# SparkFun_Servo_Trigger.net
KiCad netlist of a schematic drawn in EAGLE
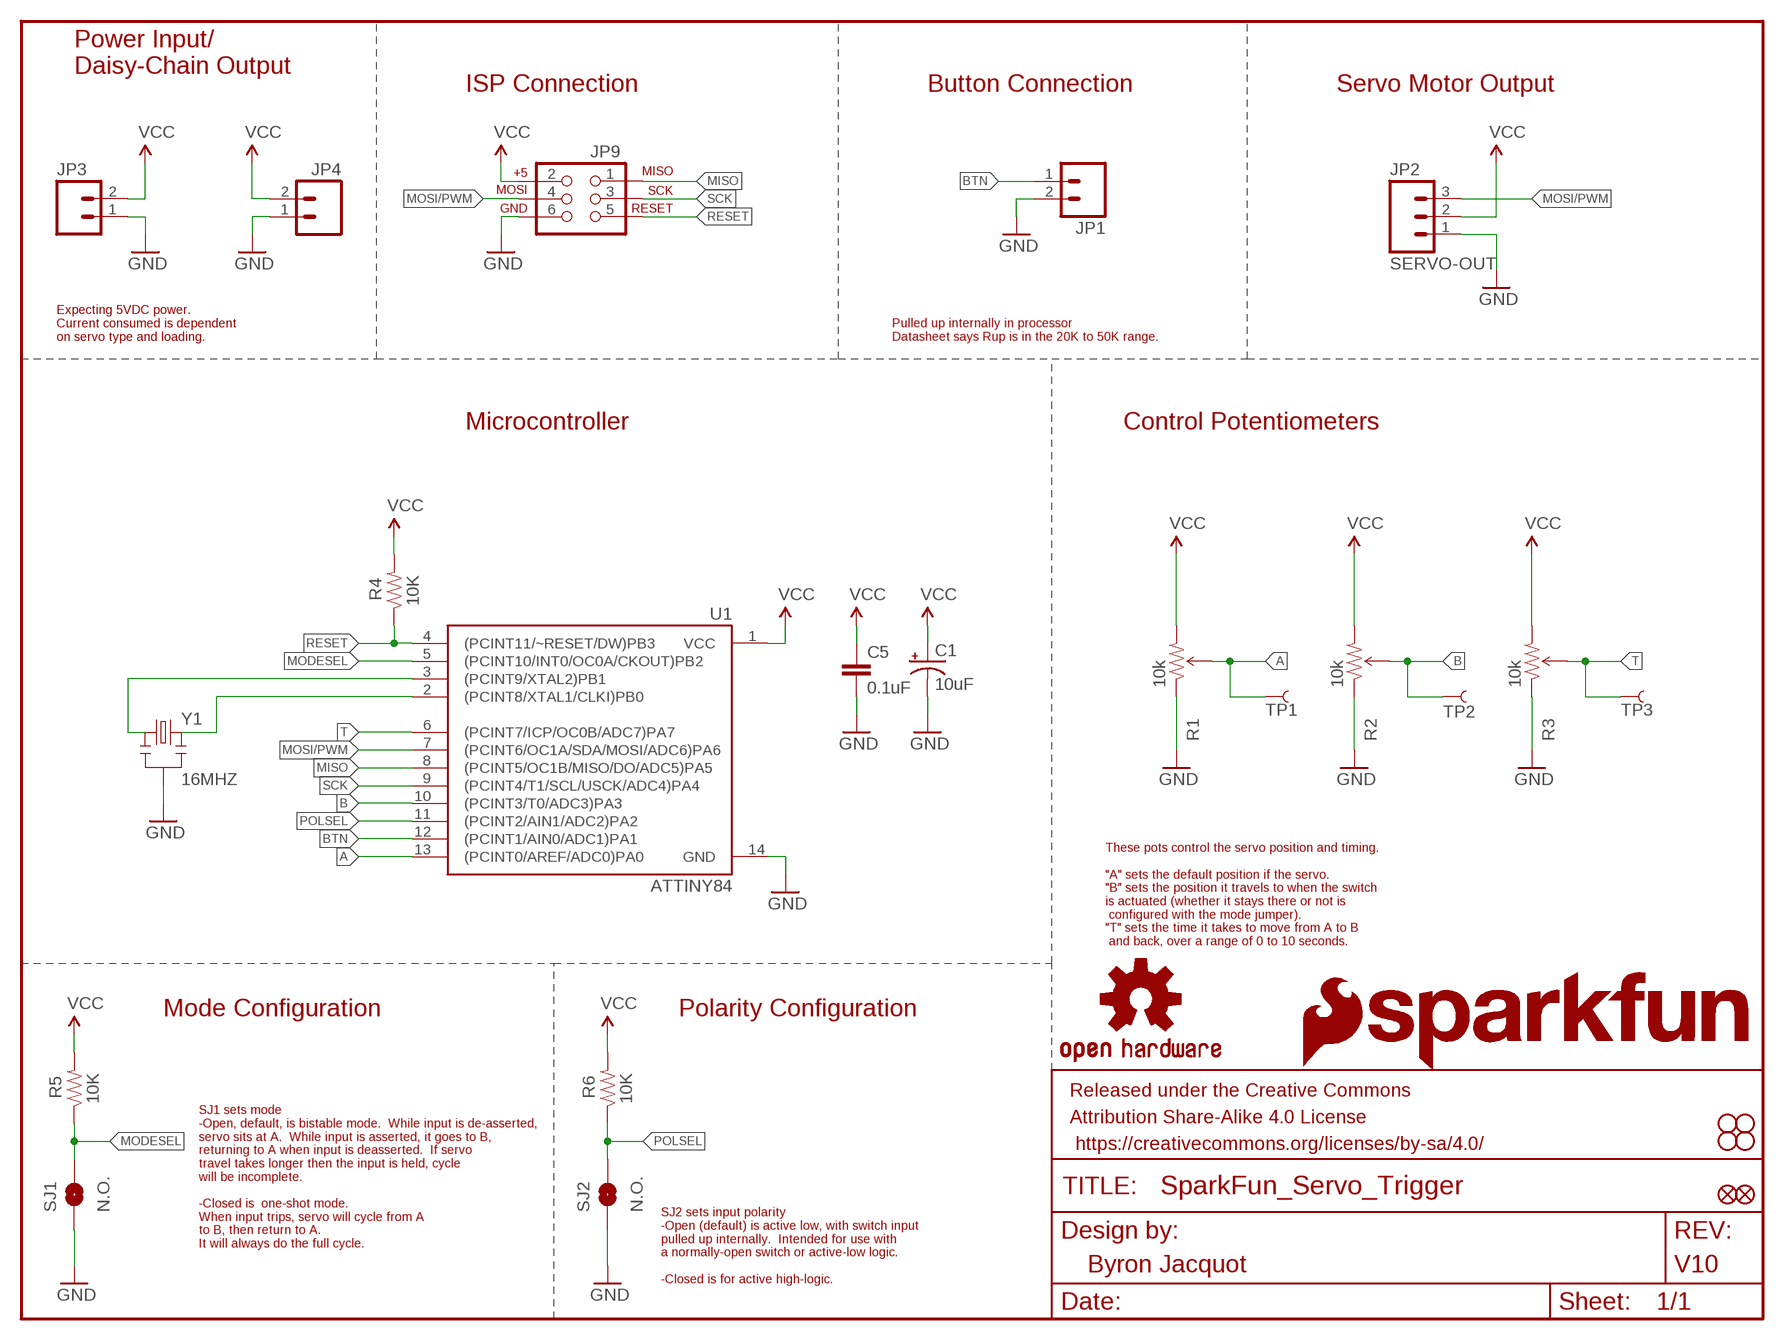
[diagram p0: schematic, sheet 1]

(export (version "E")
  (design (tool "Eeschema 10.0.6"))
  (components
    (comp (ref "C1")
      (value "10uF")
      (footprint "eagle-import:EIA3216")
      (libsource (lib "eagle-import") (part "10UF-16V-10%(TANT)"))
    )
    (comp (ref "C5")
      (value "0.1uF")
      (footprint "eagle-import:0603-CAP")
      (libsource (lib "eagle-import") (part "0.1UF-25V(+80/-20%)(0603)"))
    )
    (comp (ref "FID1")
      (value "FIDUCIAL1X2")
      (footprint "eagle-import:FIDUCIAL-1X2")
      (libsource (lib "eagle-import") (part "FIDUCIAL1X2"))
    )
    (comp (ref "FID2")
      (value "FIDUCIAL1X2")
      (footprint "eagle-import:FIDUCIAL-1X2")
      (libsource (lib "eagle-import") (part "FIDUCIAL1X2"))
    )
    (comp (ref "FRAME1")
      (value "FRAME-LETTER")
      (footprint "eagle-import:CREATIVE_COMMONS")
      (fields (field (name "DESIGNER") "Byron Jacquot") (field (name "VERSION") "V10"))
      (libsource (lib "eagle-import") (part "FRAME-LETTER"))
    )
    (comp (ref "JP1")
      (value "M021X02_NO_SILK")
      (footprint "eagle-import:1X02_NO_SILK")
      (libsource (lib "eagle-import") (part "M021X02_NO_SILK"))
    )
    (comp (ref "JP2")
      (value "SERVO-OUT")
      (footprint "eagle-import:1X03_NO_SILK")
      (libsource (lib "eagle-import") (part "M031X03_NO_SILK"))
    )
    (comp (ref "JP3")
      (value "M021X02_NO_SILK")
      (footprint "eagle-import:1X02_NO_SILK")
      (libsource (lib "eagle-import") (part "M021X02_NO_SILK"))
    )
    (comp (ref "JP4")
      (value "M021X02_NO_SILK")
      (footprint "eagle-import:1X02_NO_SILK")
      (libsource (lib "eagle-import") (part "M021X02_NO_SILK"))
    )
    (comp (ref "JP9")
      (value "AVR_SPI_PRG_6PTH")
      (footprint "eagle-import:2X3")
      (libsource (lib "eagle-import") (part "AVR_SPI_PRG_6PTH"))
    )
    (comp (ref "LOGO1")
      (value "OSHW-LOGOM")
      (footprint "eagle-import:OSHW-LOGO-M")
      (libsource (lib "eagle-import") (part "OSHW-LOGOM"))
    )
    (comp (ref "LOGO2")
      (value "SFE_LOGO_NAME.2_INCH")
      (footprint "eagle-import:SFE_LOGO_NAME_.2")
      (libsource (lib "eagle-import") (part "SFE_LOGO_NAME.2_INCH"))
    )
    (comp (ref "LOGO3")
      (value "SFE_LOGO_FLAME.2_INCH")
      (footprint "eagle-import:SFE_LOGO_FLAME_.2")
      (libsource (lib "eagle-import") (part "SFE_LOGO_FLAME.2_INCH"))
    )
    (comp (ref "R1")
      (value "10k")
      (footprint "eagle-import:TRIMPOT_5MM")
      (libsource (lib "eagle-import") (part "TRIMPOTRES-11156"))
    )
    (comp (ref "R2")
      (value "10k")
      (footprint "eagle-import:TRIMPOT_5MM")
      (libsource (lib "eagle-import") (part "TRIMPOTRES-11156"))
    )
    (comp (ref "R3")
      (value "10k")
      (footprint "eagle-import:TRIMPOT_5MM")
      (libsource (lib "eagle-import") (part "TRIMPOTRES-11156"))
    )
    (comp (ref "R4")
      (value "10K")
      (footprint "eagle-import:0603-RES")
      (libsource (lib "eagle-import") (part "10KOHM-1/10W-1%(0603)0603"))
    )
    (comp (ref "R5")
      (value "10K")
      (footprint "eagle-import:0603-RES")
      (libsource (lib "eagle-import") (part "10KOHM-1/10W-1%(0603)0603"))
    )
    (comp (ref "R6")
      (value "10K")
      (footprint "eagle-import:0603-RES")
      (libsource (lib "eagle-import") (part "10KOHM-1/10W-1%(0603)0603"))
    )
    (comp (ref "SJ1")
      (value "N.O.")
      (footprint "eagle-import:PAD-JUMPER-2-NO_YES_SILK")
      (libsource (lib "eagle-import") (part "JUMPER-PAD-2-NOYES_SILK"))
    )
    (comp (ref "SJ2")
      (value "N.O.")
      (footprint "eagle-import:PAD-JUMPER-2-NO_YES_SILK")
      (libsource (lib "eagle-import") (part "JUMPER-PAD-2-NOYES_SILK"))
    )
    (comp (ref "STANDOFF1")
      (value "STAND-OFF")
      (footprint "eagle-import:STAND-OFF")
      (libsource (lib "eagle-import") (part "STAND-OFF"))
    )
    (comp (ref "STANDOFF2")
      (value "STAND-OFF")
      (footprint "eagle-import:STAND-OFF")
      (libsource (lib "eagle-import") (part "STAND-OFF"))
    )
    (comp (ref "STANDOFF3")
      (value "STAND-OFF")
      (footprint "eagle-import:STAND-OFF")
      (libsource (lib "eagle-import") (part "STAND-OFF"))
    )
    (comp (ref "STANDOFF4")
      (value "STAND-OFF")
      (footprint "eagle-import:STAND-OFF")
      (libsource (lib "eagle-import") (part "STAND-OFF"))
    )
    (comp (ref "TP1")
      (value "TEST-POINT3X4")
      (footprint "eagle-import:PAD.03X.04")
      (libsource (lib "eagle-import") (part "TEST-POINT3X4"))
    )
    (comp (ref "TP2")
      (value "TEST-POINT3X4")
      (footprint "eagle-import:PAD.03X.04")
      (libsource (lib "eagle-import") (part "TEST-POINT3X4"))
    )
    (comp (ref "TP3")
      (value "TEST-POINT3X4")
      (footprint "eagle-import:PAD.03X.04")
      (libsource (lib "eagle-import") (part "TEST-POINT3X4"))
    )
    (comp (ref "U1")
      (value "ATTINY84")
      (footprint "eagle-import:SO14")
      (libsource (lib "eagle-import") (part "ATTINY84"))
    )
    (comp (ref "Y1")
      (value "16MHZ")
      (footprint "eagle-import:RESONATOR-SMD")
      (libsource (lib "eagle-import") (part "RESONATOR16MHZ"))
    )
  )
  (nets
    (net (code "1") (name "A") (class "Default")
      (node (ref "R1") (pin "B") (pinfunction "WIPER_B") (pintype "passive"))
      (node (ref "TP1") (pin "P$1") (pinfunction "1_P$1") (pintype "bidirectional"))
      (node (ref "U1") (pin "13") (pinfunction "(PCINT0/AREF/ADC0)PA0_13") (pintype "bidirectional"))
    )
    (net (code "2") (name "B") (class "Default")
      (node (ref "R2") (pin "B") (pinfunction "WIPER_B") (pintype "passive"))
      (node (ref "TP2") (pin "P$1") (pinfunction "1_P$1") (pintype "bidirectional"))
      (node (ref "U1") (pin "10") (pinfunction "(PCINT3/T0/ADC3)PA3_10") (pintype "bidirectional"))
    )
    (net (code "3") (name "BTN") (class "Default")
      (node (ref "JP1") (pin "1") (pinfunction "1_1") (pintype "passive"))
      (node (ref "U1") (pin "12") (pinfunction "(PCINT1/AIN0/ADC1)PA1_12") (pintype "bidirectional"))
    )
    (net (code "4") (name "GND") (class "Default")
      (node (ref "C1") (pin "C") (pinfunction "-_C") (pintype "passive"))
      (node (ref "C5") (pin "2") (pinfunction "2_2") (pintype "passive"))
      (node (ref "JP1") (pin "2") (pinfunction "2_2") (pintype "passive"))
      (node (ref "JP2") (pin "1") (pinfunction "1_1") (pintype "passive"))
      (node (ref "JP3") (pin "1") (pinfunction "1_1") (pintype "passive"))
      (node (ref "JP4") (pin "1") (pinfunction "1_1") (pintype "passive"))
      (node (ref "JP9") (pin "6") (pinfunction "6_6") (pintype "passive"))
      (node (ref "R1") (pin "A") (pinfunction "CCW_A") (pintype "passive"))
      (node (ref "R2") (pin "A") (pinfunction "CCW_A") (pintype "passive"))
      (node (ref "R3") (pin "A") (pinfunction "CCW_A") (pintype "passive"))
      (node (ref "SJ1") (pin "1") (pinfunction "1_1") (pintype "passive"))
      (node (ref "SJ2") (pin "1") (pinfunction "1_1") (pintype "passive"))
      (node (ref "U1") (pin "14") (pinfunction "GND_14") (pintype "bidirectional"))
      (node (ref "Y1") (pin "2") (pinfunction "2_2") (pintype "passive"))
    )
    (net (code "5") (name "MISO") (class "Default")
      (node (ref "JP9") (pin "1") (pinfunction "1_1") (pintype "passive"))
      (node (ref "U1") (pin "8") (pinfunction "(PCINT5/OC1B/MISO/DO/ADC5)PA5_8") (pintype "bidirectional"))
    )
    (net (code "6") (name "MODESEL") (class "Default")
      (node (ref "R5") (pin "1") (pinfunction "1_1") (pintype "passive"))
      (node (ref "SJ1") (pin "2") (pinfunction "2_2") (pintype "passive"))
      (node (ref "U1") (pin "5") (pinfunction "(PCINT10/INT0/OC0A/CKOUT)PB2_5") (pintype "bidirectional"))
    )
    (net (code "7") (name "MOSI{slash}PWM") (class "Default")
      (node (ref "JP2") (pin "3") (pinfunction "3_3") (pintype "passive"))
      (node (ref "JP9") (pin "4") (pinfunction "4_4") (pintype "passive"))
      (node (ref "U1") (pin "7") (pinfunction "(PCINT6/OC1A/SDA/MOSI/ADC6)PA6_7") (pintype "bidirectional"))
    )
    (net (code "8") (name "Net-(U1-(PCINT8{slash}XTAL1{slash}CLKI)PB0)") (class "Default")
      (node (ref "U1") (pin "2") (pinfunction "(PCINT8/XTAL1/CLKI)PB0_2") (pintype "bidirectional"))
      (node (ref "Y1") (pin "3") (pinfunction "3_3") (pintype "passive"))
    )
    (net (code "9") (name "Net-(U1-(PCINT9{slash}XTAL2)PB1)") (class "Default")
      (node (ref "U1") (pin "3") (pinfunction "(PCINT9/XTAL2)PB1_3") (pintype "bidirectional"))
      (node (ref "Y1") (pin "1") (pinfunction "1_1") (pintype "passive"))
    )
    (net (code "10") (name "POLSEL") (class "Default")
      (node (ref "R6") (pin "1") (pinfunction "1_1") (pintype "passive"))
      (node (ref "SJ2") (pin "2") (pinfunction "2_2") (pintype "passive"))
      (node (ref "U1") (pin "11") (pinfunction "(PCINT2/AIN1/ADC2)PA2_11") (pintype "bidirectional"))
    )
    (net (code "11") (name "RESET") (class "Default")
      (node (ref "JP9") (pin "5") (pinfunction "5_5") (pintype "passive"))
      (node (ref "R4") (pin "1") (pinfunction "1_1") (pintype "passive"))
      (node (ref "U1") (pin "4") (pinfunction "(PCINT11/~{RESET/DW})PB3_4") (pintype "bidirectional"))
    )
    (net (code "12") (name "SCK") (class "Default")
      (node (ref "JP9") (pin "3") (pinfunction "3_3") (pintype "passive"))
      (node (ref "U1") (pin "9") (pinfunction "(PCINT4/T1/SCL/USCK/ADC4)PA4_9") (pintype "bidirectional"))
    )
    (net (code "13") (name "T") (class "Default")
      (node (ref "R3") (pin "B") (pinfunction "WIPER_B") (pintype "passive"))
      (node (ref "TP3") (pin "P$1") (pinfunction "1_P$1") (pintype "bidirectional"))
      (node (ref "U1") (pin "6") (pinfunction "(PCINT7/ICP/OC0B/ADC7)PA7_6") (pintype "bidirectional"))
    )
    (net (code "14") (name "VCC") (class "Default")
      (node (ref "C1") (pin "A") (pinfunction "+_A") (pintype "passive"))
      (node (ref "C5") (pin "1") (pinfunction "1_1") (pintype "passive"))
      (node (ref "JP2") (pin "2") (pinfunction "2_2") (pintype "passive"))
      (node (ref "JP3") (pin "2") (pinfunction "2_2") (pintype "passive"))
      (node (ref "JP4") (pin "2") (pinfunction "2_2") (pintype "passive"))
      (node (ref "JP9") (pin "2") (pinfunction "2_2") (pintype "passive"))
      (node (ref "R1") (pin "C") (pinfunction "CW_C") (pintype "passive"))
      (node (ref "R2") (pin "C") (pinfunction "CW_C") (pintype "passive"))
      (node (ref "R3") (pin "C") (pinfunction "CW_C") (pintype "passive"))
      (node (ref "R4") (pin "2") (pinfunction "2_2") (pintype "passive"))
      (node (ref "R5") (pin "2") (pinfunction "2_2") (pintype "passive"))
      (node (ref "R6") (pin "2") (pinfunction "2_2") (pintype "passive"))
      (node (ref "U1") (pin "1") (pinfunction "VCC_1") (pintype "bidirectional"))
    )
  )
)
